# stepper_fw_bw_w_nand.net
KiCad netlist of a schematic drawn in EAGLE
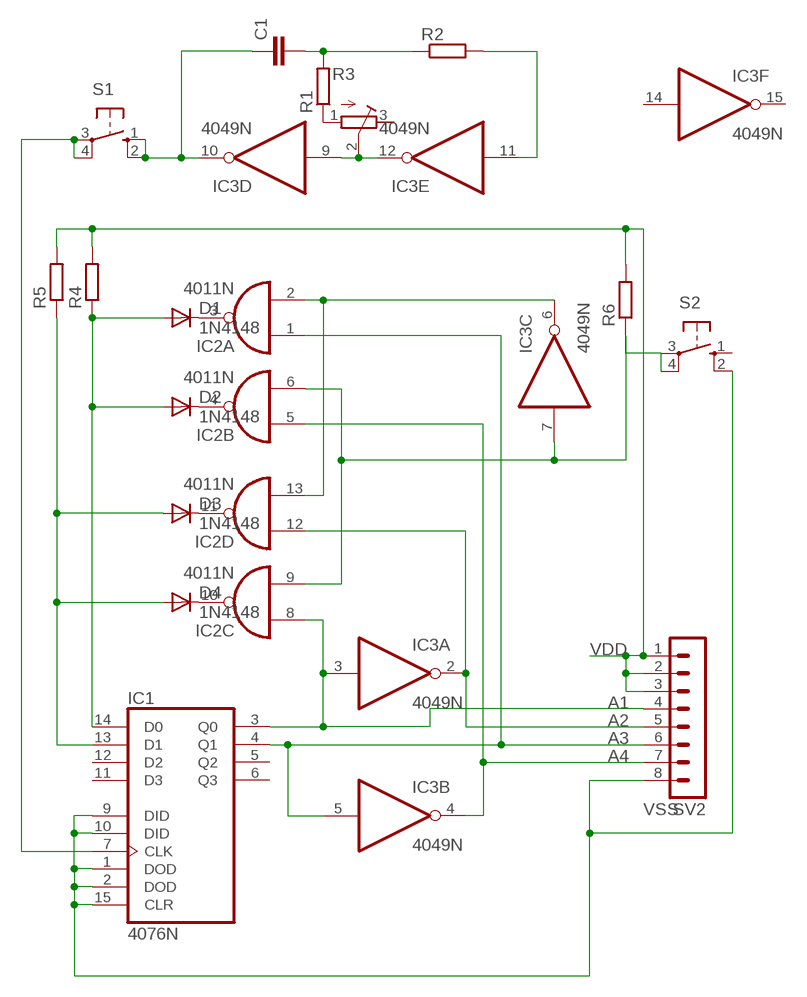
[diagram p0: schematic, sheet 1]

(export (version "E")
  (design (tool "Eeschema 10.0.6"))
  (components
    (comp (ref "C1")
      (value "C-EU050-024X044")
      (footprint "eagle-import:C050-024X044")
      (libsource (lib "eagle-import") (part "C-EU050-024X044"))
    )
    (comp (ref "D1")
      (value "1N4148")
      (footprint "eagle-import:DO35-7")
      (libsource (lib "eagle-import") (part "1N4148DO35-7"))
    )
    (comp (ref "D2")
      (value "1N4148")
      (footprint "eagle-import:DO35-7")
      (libsource (lib "eagle-import") (part "1N4148DO35-7"))
    )
    (comp (ref "D3")
      (value "1N4148")
      (footprint "eagle-import:DO35-7")
      (libsource (lib "eagle-import") (part "1N4148DO35-7"))
    )
    (comp (ref "D4")
      (value "1N4148")
      (footprint "eagle-import:DO35-7")
      (libsource (lib "eagle-import") (part "1N4148DO35-7"))
    )
    (comp (ref "IC1")
      (value "4076N")
      (footprint "eagle-import:DIL16")
      (libsource (lib "eagle-import") (part "4076N"))
    )
    (comp (ref "IC2")
      (value "4011N")
      (footprint "eagle-import:DIL14")
      (libsource (lib "eagle-import") (part "4011N"))
    )
    (comp (ref "IC3")
      (value "4049N")
      (footprint "eagle-import:DIL16")
      (libsource (lib "eagle-import") (part "4049N"))
    )
    (comp (ref "R1")
      (value "R-EU_0207/10")
      (footprint "eagle-import:0207_10")
      (libsource (lib "eagle-import") (part "R-EU_0207/10"))
    )
    (comp (ref "R2")
      (value "R-EU_0207/10")
      (footprint "eagle-import:0207_10")
      (libsource (lib "eagle-import") (part "R-EU_0207/10"))
    )
    (comp (ref "R3")
      (value "R-TRIMM64W")
      (footprint "eagle-import:RTRIM64W")
      (libsource (lib "eagle-import") (part "R-TRIMM64W"))
    )
    (comp (ref "R4")
      (value "R-EU_0207/10")
      (footprint "eagle-import:0207_10")
      (libsource (lib "eagle-import") (part "R-EU_0207/10"))
    )
    (comp (ref "R5")
      (value "R-EU_0207/10")
      (footprint "eagle-import:0207_10")
      (libsource (lib "eagle-import") (part "R-EU_0207/10"))
    )
    (comp (ref "R6")
      (value "R-EU_0207/10")
      (footprint "eagle-import:0207_10")
      (libsource (lib "eagle-import") (part "R-EU_0207/10"))
    )
    (comp (ref "S1")
      (value "40-XX")
      (footprint "eagle-import:B3F-40XX")
      (fields (field (name "MF") "OMRON COMPONENTS USA") (field (name "MPN") "B3F-4000"))
      (libsource (lib "eagle-import") (part "40-XX"))
    )
    (comp (ref "S2")
      (value "40-XX")
      (footprint "eagle-import:B3F-40XX")
      (fields (field (name "MF") "OMRON COMPONENTS USA") (field (name "MPN") "B3F-4000"))
      (libsource (lib "eagle-import") (part "40-XX"))
    )
    (comp (ref "SV2")
      (value "MA08-1")
      (footprint "eagle-import:MA08-1")
      (libsource (lib "eagle-import") (part "MA08-1"))
    )
  )
  (nets
    (net (code "1") (name "/A1") (class "Default")
      (node (ref "IC1") (pin "3") (pinfunction "Q0_3") (pintype "output"))
      (node (ref "IC2") (pin "8") (pinfunction "I0_8") (pintype "input"))
      (node (ref "IC3") (pin "3") (pinfunction "I_3") (pintype "input"))
      (node (ref "SV2") (pin "4") (pinfunction "4_4") (pintype "passive"))
    )
    (net (code "2") (name "/A2") (class "Default")
      (node (ref "IC2") (pin "12") (pinfunction "I0_12") (pintype "input"))
      (node (ref "IC3") (pin "2") (pinfunction "O_2") (pintype "output"))
      (node (ref "SV2") (pin "5") (pinfunction "5_5") (pintype "passive"))
    )
    (net (code "3") (name "/A3") (class "Default")
      (node (ref "IC1") (pin "4") (pinfunction "Q1_4") (pintype "output"))
      (node (ref "IC2") (pin "1") (pinfunction "I0_1") (pintype "input"))
      (node (ref "IC3") (pin "5") (pinfunction "I_5") (pintype "input"))
      (node (ref "SV2") (pin "6") (pinfunction "6_6") (pintype "passive"))
    )
    (net (code "4") (name "/A4") (class "Default")
      (node (ref "IC2") (pin "5") (pinfunction "I0_5") (pintype "input"))
      (node (ref "IC3") (pin "4") (pinfunction "O_4") (pintype "output"))
      (node (ref "SV2") (pin "7") (pinfunction "7_7") (pintype "passive"))
    )
    (net (code "5") (name "/VDD") (class "Default")
      (node (ref "R4") (pin "2") (pinfunction "2_2") (pintype "passive"))
      (node (ref "R5") (pin "2") (pinfunction "2_2") (pintype "passive"))
      (node (ref "R6") (pin "2") (pinfunction "2_2") (pintype "passive"))
      (node (ref "SV2") (pin "1") (pinfunction "1_1") (pintype "passive"))
      (node (ref "SV2") (pin "2") (pinfunction "2_2") (pintype "passive"))
      (node (ref "SV2") (pin "3") (pinfunction "3_3") (pintype "passive"))
    )
    (net (code "6") (name "/VSS") (class "Default")
      (node (ref "IC1") (pin "1") (pinfunction "DOD_1") (pintype "input"))
      (node (ref "IC1") (pin "10") (pinfunction "DID_10") (pintype "input"))
      (node (ref "IC1") (pin "15") (pinfunction "CLR_15") (pintype "input"))
      (node (ref "IC1") (pin "2") (pinfunction "DOD_2") (pintype "input"))
      (node (ref "IC1") (pin "9") (pinfunction "DID_9") (pintype "input"))
      (node (ref "S2") (pin "2") (pinfunction "S1_2") (pintype "passive"))
      (node (ref "SV2") (pin "8") (pinfunction "8_8") (pintype "passive"))
    )
    (net (code "7") (name "Net-(C1-Pad2)") (class "Default")
      (node (ref "C1") (pin "2") (pinfunction "2_2") (pintype "passive"))
      (node (ref "R1") (pin "2") (pinfunction "2_2") (pintype "passive"))
      (node (ref "R2") (pin "1") (pinfunction "1_1") (pintype "passive"))
    )
    (net (code "8") (name "Net-(IC1A-CLK)") (class "Default")
      (node (ref "IC1") (pin "7") (pinfunction "CLK_7") (pintype "input"))
      (node (ref "S1") (pin "3") (pinfunction "P_3") (pintype "passive"))
      (node (ref "S1") (pin "4") (pinfunction "P1_4") (pintype "passive"))
    )
    (net (code "9") (name "Net-(IC1A-D0)") (class "Default")
      (node (ref "D1") (pin "A") (pinfunction "A_A") (pintype "passive"))
      (node (ref "D2") (pin "A") (pinfunction "A_A") (pintype "passive"))
      (node (ref "IC1") (pin "14") (pinfunction "D0_14") (pintype "input"))
      (node (ref "R4") (pin "1") (pinfunction "1_1") (pintype "passive"))
    )
    (net (code "10") (name "Net-(IC1A-D1)") (class "Default")
      (node (ref "D3") (pin "A") (pinfunction "A_A") (pintype "passive"))
      (node (ref "D4") (pin "A") (pinfunction "A_A") (pintype "passive"))
      (node (ref "IC1") (pin "13") (pinfunction "D1_13") (pintype "input"))
      (node (ref "R5") (pin "1") (pinfunction "1_1") (pintype "passive"))
    )
    (net (code "11") (name "Net-(IC2A-I1)") (class "Default")
      (node (ref "IC2") (pin "13") (pinfunction "I1_13") (pintype "input"))
      (node (ref "IC2") (pin "2") (pinfunction "I1_2") (pintype "input"))
      (node (ref "IC3") (pin "6") (pinfunction "O_6") (pintype "output"))
    )
    (net (code "12") (name "Net-(IC2A-O)") (class "Default")
      (node (ref "D1") (pin "C") (pinfunction "C_C") (pintype "passive"))
      (node (ref "IC2") (pin "3") (pinfunction "O_3") (pintype "output"))
    )
    (net (code "13") (name "Net-(IC2B-I1)") (class "Default")
      (node (ref "IC2") (pin "6") (pinfunction "I1_6") (pintype "input"))
      (node (ref "IC2") (pin "9") (pinfunction "I1_9") (pintype "input"))
      (node (ref "IC3") (pin "7") (pinfunction "I_7") (pintype "input"))
      (node (ref "R6") (pin "1") (pinfunction "1_1") (pintype "passive"))
      (node (ref "S2") (pin "3") (pinfunction "P_3") (pintype "passive"))
      (node (ref "S2") (pin "4") (pinfunction "P1_4") (pintype "passive"))
    )
    (net (code "14") (name "Net-(IC2B-O)") (class "Default")
      (node (ref "D2") (pin "C") (pinfunction "C_C") (pintype "passive"))
      (node (ref "IC2") (pin "4") (pinfunction "O_4") (pintype "output"))
    )
    (net (code "15") (name "Net-(IC2C-O)") (class "Default")
      (node (ref "D4") (pin "C") (pinfunction "C_C") (pintype "passive"))
      (node (ref "IC2") (pin "10") (pinfunction "O_10") (pintype "output"))
    )
    (net (code "16") (name "Net-(IC2D-O)") (class "Default")
      (node (ref "D3") (pin "C") (pinfunction "C_C") (pintype "passive"))
      (node (ref "IC2") (pin "11") (pinfunction "O_11") (pintype "output"))
    )
    (net (code "17") (name "Net-(IC3D-I)") (class "Default")
      (node (ref "IC3") (pin "12") (pinfunction "O_12") (pintype "output"))
      (node (ref "IC3") (pin "9") (pinfunction "I_9") (pintype "input"))
      (node (ref "R3") (pin "2") (pinfunction "S_2") (pintype "passive"))
    )
    (net (code "18") (name "Net-(IC3D-O)") (class "Default")
      (node (ref "C1") (pin "1") (pinfunction "1_1") (pintype "passive"))
      (node (ref "IC3") (pin "10") (pinfunction "O_10") (pintype "output"))
      (node (ref "S1") (pin "1") (pinfunction "S_1") (pintype "passive"))
      (node (ref "S1") (pin "2") (pinfunction "S1_2") (pintype "passive"))
    )
    (net (code "19") (name "Net-(IC3E-I)") (class "Default")
      (node (ref "IC3") (pin "11") (pinfunction "I_11") (pintype "input"))
      (node (ref "R2") (pin "2") (pinfunction "2_2") (pintype "passive"))
    )
    (net (code "20") (name "Net-(R3-A)") (class "Default")
      (node (ref "R1") (pin "1") (pinfunction "1_1") (pintype "passive"))
      (node (ref "R3") (pin "1") (pinfunction "A_1") (pintype "passive"))
    )
    (net (code "21") (name "unconnected-(IC1A-D2-Pad12)") (class "Default")
      (node (ref "IC1") (pin "12") (pinfunction "D2_12") (pintype "input"))
    )
    (net (code "22") (name "unconnected-(IC1A-D3-Pad11)") (class "Default")
      (node (ref "IC1") (pin "11") (pinfunction "D3_11") (pintype "input"))
    )
    (net (code "23") (name "unconnected-(IC1A-Q2-Pad5)") (class "Default")
      (node (ref "IC1") (pin "5") (pinfunction "Q2_5") (pintype "output"))
    )
    (net (code "24") (name "unconnected-(IC1A-Q3-Pad6)") (class "Default")
      (node (ref "IC1") (pin "6") (pinfunction "Q3_6") (pintype "output"))
    )
    (net (code "25") (name "unconnected-(IC3F-I-Pad14)") (class "Default")
      (node (ref "IC3") (pin "14") (pinfunction "I_14") (pintype "input"))
    )
    (net (code "26") (name "unconnected-(IC3F-O-Pad15)") (class "Default")
      (node (ref "IC3") (pin "15") (pinfunction "O_15") (pintype "output"))
    )
    (net (code "27") (name "unconnected-(R3-E-Pad3)") (class "Default")
      (node (ref "R3") (pin "3") (pinfunction "E_3") (pintype "passive"))
    )
    (net (code "28") (name "unconnected-(S2-S-Pad1)") (class "Default")
      (node (ref "S2") (pin "1") (pinfunction "S_1") (pintype "passive"))
    )
  )
)
